# controller_connectors.net
KiCad netlist of a schematic drawn in EAGLE
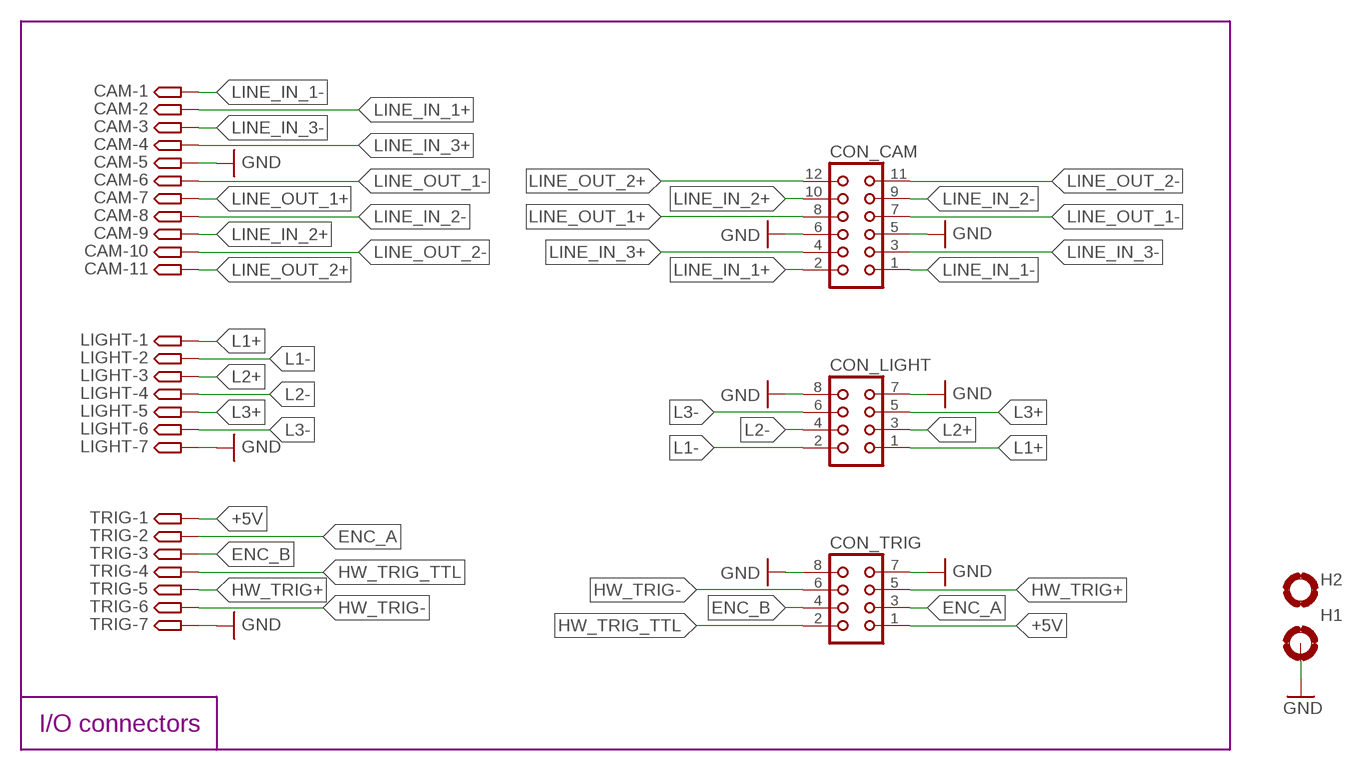
[diagram p0: schematic, sheet 1]

(export (version "E")
  (design (tool "Eeschema 10.0.6"))
  (components
    (comp (ref "CAM")
      (value "SMPAD-11")
      (footprint "eagle-import:S-11P")
      (libsource (lib "eagle-import") (part "SMPAD-11"))
    )
    (comp (ref "CON_CAM")
      (value "CON12")
      (footprint "eagle-import:CON12_2MM")
      (libsource (lib "eagle-import") (part "CON12"))
    )
    (comp (ref "CON_LIGHT")
      (value "CON8")
      (footprint "eagle-import:CON8_2MM")
      (libsource (lib "eagle-import") (part "CON8"))
    )
    (comp (ref "CON_TRIG")
      (value "CON8")
      (footprint "eagle-import:CON8_2MM")
      (libsource (lib "eagle-import") (part "CON8"))
    )
    (comp (ref "H1")
      (value "HOLE-3MM_PLATED")
      (footprint "eagle-import:3MM_PLATED")
      (libsource (lib "eagle-import") (part "HOLE-3MM_PLATED"))
    )
    (comp (ref "H2")
      (value "HOLE_UNPLATED")
      (footprint "eagle-import:3MM_UNPLATED_1SIDE")
      (libsource (lib "eagle-import") (part "HOLE_UNPLATED"))
    )
    (comp (ref "LIGHT")
      (value "SMPAD-7")
      (footprint "eagle-import:S-7P")
      (libsource (lib "eagle-import") (part "SMPAD-7"))
    )
    (comp (ref "TRIG")
      (value "SMPAD-7")
      (footprint "eagle-import:S-7P")
      (libsource (lib "eagle-import") (part "SMPAD-7"))
    )
  )
  (nets
    (net (code "1") (name "+5V") (class "Default")
      (node (ref "CON_TRIG") (pin "1") (pinfunction "1_1") (pintype "passive"))
      (node (ref "TRIG") (pin "1") (pinfunction "P_1") (pintype "passive"))
    )
    (net (code "2") (name "ENC_A") (class "Default")
      (node (ref "CON_TRIG") (pin "3") (pinfunction "3_3") (pintype "passive"))
      (node (ref "TRIG") (pin "2") (pinfunction "P_2") (pintype "passive"))
    )
    (net (code "3") (name "ENC_B") (class "Default")
      (node (ref "CON_TRIG") (pin "4") (pinfunction "4_4") (pintype "passive"))
      (node (ref "TRIG") (pin "3") (pinfunction "P_3") (pintype "passive"))
    )
    (net (code "4") (name "GND") (class "Default")
      (node (ref "CAM") (pin "5") (pinfunction "P_5") (pintype "passive"))
      (node (ref "CON_CAM") (pin "5") (pinfunction "5_5") (pintype "passive"))
      (node (ref "CON_CAM") (pin "6") (pinfunction "6_6") (pintype "passive"))
      (node (ref "CON_LIGHT") (pin "7") (pinfunction "7_7") (pintype "passive"))
      (node (ref "CON_LIGHT") (pin "8") (pinfunction "8_8") (pintype "passive"))
      (node (ref "CON_TRIG") (pin "7") (pinfunction "7_7") (pintype "passive"))
      (node (ref "CON_TRIG") (pin "8") (pinfunction "8_8") (pintype "passive"))
      (node (ref "H1") (pin "1") (pinfunction "MOUNT_1") (pintype "passive"))
      (node (ref "LIGHT") (pin "7") (pinfunction "P_7") (pintype "passive"))
      (node (ref "TRIG") (pin "7") (pinfunction "P_7") (pintype "passive"))
    )
    (net (code "5") (name "HW_TRIG+") (class "Default")
      (node (ref "CON_TRIG") (pin "5") (pinfunction "5_5") (pintype "passive"))
      (node (ref "TRIG") (pin "5") (pinfunction "P_5") (pintype "passive"))
    )
    (net (code "6") (name "HW_TRIG-") (class "Default")
      (node (ref "CON_TRIG") (pin "6") (pinfunction "6_6") (pintype "passive"))
      (node (ref "TRIG") (pin "6") (pinfunction "P_6") (pintype "passive"))
    )
    (net (code "7") (name "HW_TRIG_TTL") (class "Default")
      (node (ref "CON_TRIG") (pin "2") (pinfunction "2_2") (pintype "passive"))
      (node (ref "TRIG") (pin "4") (pinfunction "P_4") (pintype "passive"))
    )
    (net (code "8") (name "L1+") (class "Default")
      (node (ref "CON_LIGHT") (pin "1") (pinfunction "1_1") (pintype "passive"))
      (node (ref "LIGHT") (pin "1") (pinfunction "P_1") (pintype "passive"))
    )
    (net (code "9") (name "L1-") (class "Default")
      (node (ref "CON_LIGHT") (pin "2") (pinfunction "2_2") (pintype "passive"))
      (node (ref "LIGHT") (pin "2") (pinfunction "P_2") (pintype "passive"))
    )
    (net (code "10") (name "L2+") (class "Default")
      (node (ref "CON_LIGHT") (pin "3") (pinfunction "3_3") (pintype "passive"))
      (node (ref "LIGHT") (pin "3") (pinfunction "P_3") (pintype "passive"))
    )
    (net (code "11") (name "L2-") (class "Default")
      (node (ref "CON_LIGHT") (pin "4") (pinfunction "4_4") (pintype "passive"))
      (node (ref "LIGHT") (pin "4") (pinfunction "P_4") (pintype "passive"))
    )
    (net (code "12") (name "L3+") (class "Default")
      (node (ref "CON_LIGHT") (pin "5") (pinfunction "5_5") (pintype "passive"))
      (node (ref "LIGHT") (pin "5") (pinfunction "P_5") (pintype "passive"))
    )
    (net (code "13") (name "L3-") (class "Default")
      (node (ref "CON_LIGHT") (pin "6") (pinfunction "6_6") (pintype "passive"))
      (node (ref "LIGHT") (pin "6") (pinfunction "P_6") (pintype "passive"))
    )
    (net (code "14") (name "LINE_IN_1+") (class "Default")
      (node (ref "CAM") (pin "2") (pinfunction "P_2") (pintype "passive"))
      (node (ref "CON_CAM") (pin "2") (pinfunction "2_2") (pintype "passive"))
    )
    (net (code "15") (name "LINE_IN_1-") (class "Default")
      (node (ref "CAM") (pin "1") (pinfunction "P_1") (pintype "passive"))
      (node (ref "CON_CAM") (pin "1") (pinfunction "1_1") (pintype "passive"))
    )
    (net (code "16") (name "LINE_IN_2+") (class "Default")
      (node (ref "CAM") (pin "9") (pinfunction "P_9") (pintype "passive"))
      (node (ref "CON_CAM") (pin "10") (pinfunction "10_10") (pintype "passive"))
    )
    (net (code "17") (name "LINE_IN_2-") (class "Default")
      (node (ref "CAM") (pin "8") (pinfunction "P_8") (pintype "passive"))
      (node (ref "CON_CAM") (pin "9") (pinfunction "9_9") (pintype "passive"))
    )
    (net (code "18") (name "LINE_IN_3+") (class "Default")
      (node (ref "CAM") (pin "4") (pinfunction "P_4") (pintype "passive"))
      (node (ref "CON_CAM") (pin "4") (pinfunction "4_4") (pintype "passive"))
    )
    (net (code "19") (name "LINE_IN_3-") (class "Default")
      (node (ref "CAM") (pin "3") (pinfunction "P_3") (pintype "passive"))
      (node (ref "CON_CAM") (pin "3") (pinfunction "3_3") (pintype "passive"))
    )
    (net (code "20") (name "LINE_OUT_1+") (class "Default")
      (node (ref "CAM") (pin "7") (pinfunction "P_7") (pintype "passive"))
      (node (ref "CON_CAM") (pin "8") (pinfunction "8_8") (pintype "passive"))
    )
    (net (code "21") (name "LINE_OUT_1-") (class "Default")
      (node (ref "CAM") (pin "6") (pinfunction "P_6") (pintype "passive"))
      (node (ref "CON_CAM") (pin "7") (pinfunction "7_7") (pintype "passive"))
    )
    (net (code "22") (name "LINE_OUT_2+") (class "Default")
      (node (ref "CAM") (pin "11") (pinfunction "P_11") (pintype "passive"))
      (node (ref "CON_CAM") (pin "12") (pinfunction "12_12") (pintype "passive"))
    )
    (net (code "23") (name "LINE_OUT_2-") (class "Default")
      (node (ref "CAM") (pin "10") (pinfunction "P_10") (pintype "passive"))
      (node (ref "CON_CAM") (pin "11") (pinfunction "11_11") (pintype "passive"))
    )
  )
)
